# 03_-Main_Processor.net
KiCad netlist of a schematic drawn in Altium Designer
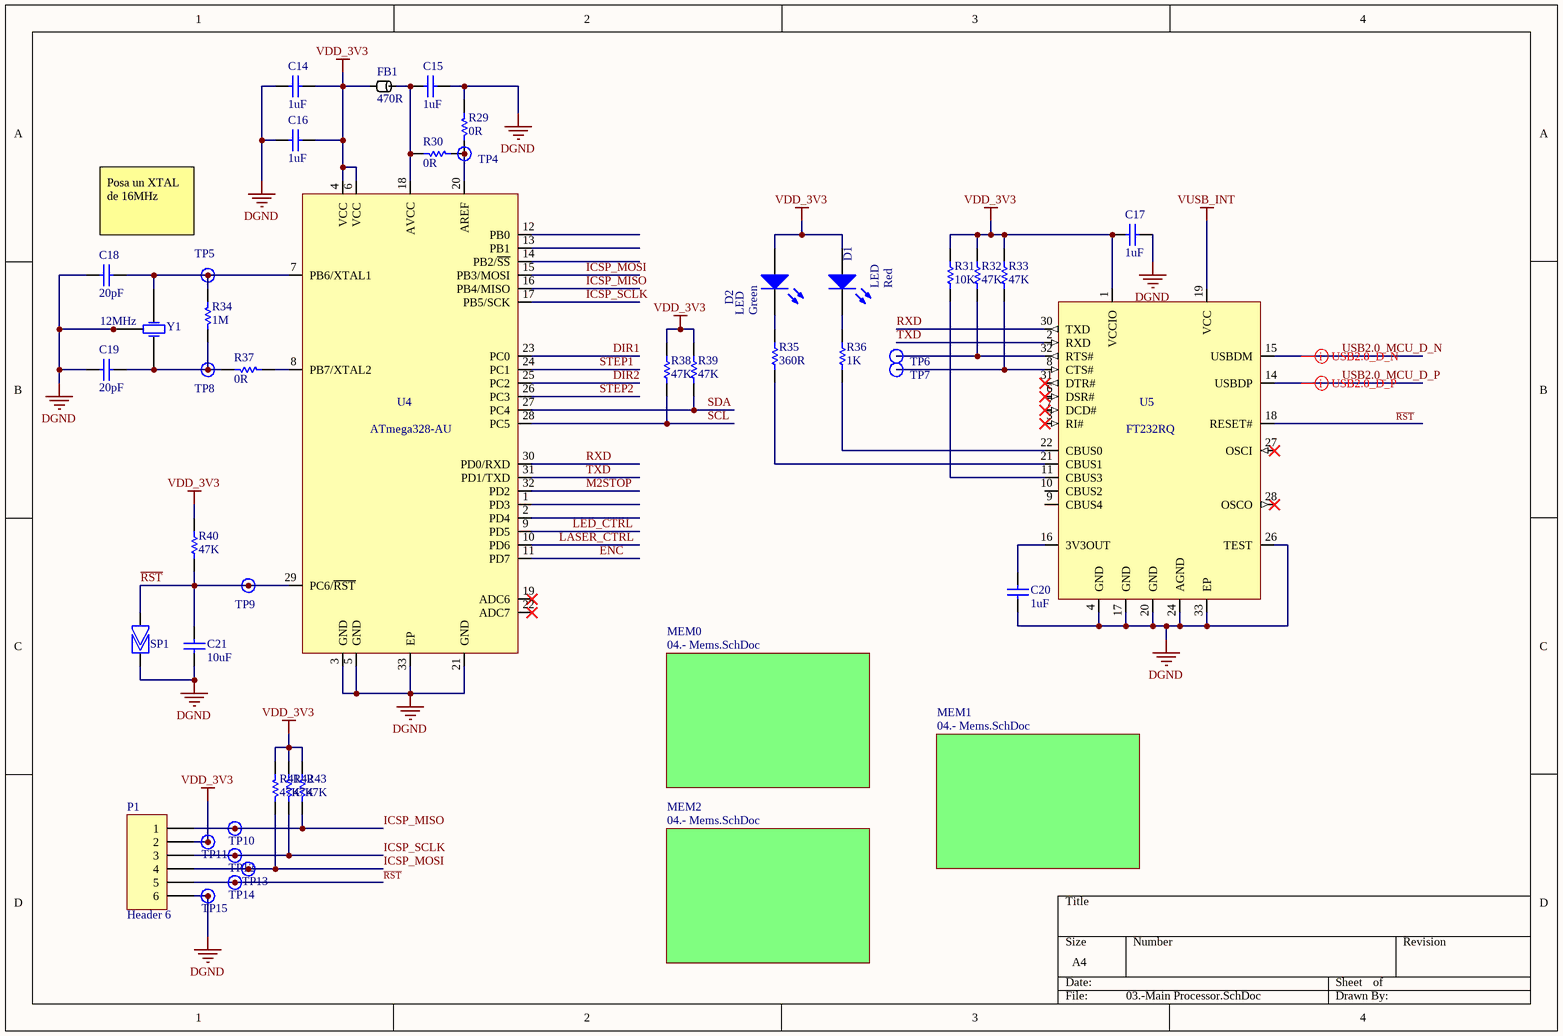
[diagram p0: 03.-Main Processor.SchDoc]

(export (version "E")
  (design (tool "Eeschema 10.0.6"))
  (components
    (comp (ref "C14")
      (value "1uF")
      (footprint "CAPC1005N")
      (description "COND. CER.1uF X5R 16V 0402")
      (fields
        (field (name "PART NUMBER") "ISR01020111")
        (field (name "VOLTAGE") "16V")
        (field (name "PUBLISHER") "Altium Limited")
        (field (name "LIBRARY PATH") "SIMBOLS_PASSIUS.SCHLIB")
      )
      (libsource (lib "MAIN_CSE") (part "CAP-NP"))
    )
    (comp (ref "C15")
      (value "1uF")
      (footprint "CAPC1005N")
      (description "COND. CER.1uF X5R 16V 0402")
      (fields
        (field (name "PART NUMBER") "ISR01020111")
        (field (name "VOLTAGE") "16V")
        (field (name "PUBLISHER") "Altium Limited")
        (field (name "LIBRARY PATH") "SIMBOLS_PASSIUS.SCHLIB")
      )
      (libsource (lib "MAIN_CSE") (part "CAP-NP"))
    )
    (comp (ref "C16")
      (value "1uF")
      (footprint "CAPC1005N")
      (description "COND. CER.1uF X5R 16V 0402")
      (fields
        (field (name "PART NUMBER") "ISR01020111")
        (field (name "VOLTAGE") "16V")
        (field (name "PUBLISHER") "Altium Limited")
        (field (name "LIBRARY PATH") "SIMBOLS_PASSIUS.SCHLIB")
      )
      (libsource (lib "MAIN_CSE") (part "CAP-NP"))
    )
    (comp (ref "C17")
      (value "1uF")
      (footprint "CAPC1005N")
      (description "COND. CER.1uF X5R 16V 0402")
      (fields
        (field (name "PART NUMBER") "ISR01020111")
        (field (name "VOLTAGE") "16V")
        (field (name "PUBLISHER") "Altium Limited")
        (field (name "LIBRARY PATH") "SIMBOLS_PASSIUS.SCHLIB")
      )
      (libsource (lib "MAIN_CSE") (part "CAP-NP"))
    )
    (comp (ref "C18")
      (value "20pF")
      (footprint "CAPC1608N")
      (description "COND. SMD 20P COG 50V 0603")
      (fields
        (field (name "PART NUMBER") "ISR01020103")
        (field (name "VOLTAGE") "50V")
        (field (name "PUBLISHER") "Altium Limited")
        (field (name "LIBRARY PATH") "SIMBOLS_PASSIUS.SCHLIB")
      )
      (libsource (lib "MAIN_CSE") (part "CAP-NP"))
    )
    (comp (ref "C19")
      (value "20pF")
      (footprint "CAPC1608N")
      (description "COND. SMD 20P COG 50V 0603")
      (fields
        (field (name "PART NUMBER") "ISR01020103")
        (field (name "VOLTAGE") "50V")
        (field (name "PUBLISHER") "Altium Limited")
        (field (name "LIBRARY PATH") "SIMBOLS_PASSIUS.SCHLIB")
      )
      (libsource (lib "MAIN_CSE") (part "CAP-NP"))
    )
    (comp (ref "C20")
      (value "1uF")
      (footprint "CAPC1005N")
      (description "COND. CER.1uF X5R 16V 0402")
      (fields
        (field (name "PART NUMBER") "ISR01020111")
        (field (name "VOLTAGE") "16V")
        (field (name "PUBLISHER") "Altium Limited")
        (field (name "LIBRARY PATH") "SIMBOLS_PASSIUS.SCHLIB")
      )
      (libsource (lib "MAIN_CSE") (part "CAP-NP"))
    )
    (comp (ref "C21")
      (value "10uF")
      (footprint "CAPC1608N")
      (description "COND. SMD 10uF X5R 6V3 0603")
      (fields
        (field (name "PART NUMBER") "ISR01020094")
        (field (name "VOLTAGE") "6V3")
        (field (name "PUBLISHER") "Altium Limited")
        (field (name "LIBRARY PATH") "SIMBOLS_PASSIUS.SCHLIB")
      )
      (libsource (lib "MAIN_CSE") (part "CAP-NP"))
    )
    (comp (ref "D1")
      (value "LED")
      (footprint "LED_1206")
      (description "LUXEON Z Vermell 1A 3.15V")
      (fields
        (field (name "PART NUMBER") "LXZ1-PD01")
        (field (name "COLOR1") "Red")
        (field (name "LIBRARY PATH") "SIMBOLS_SEMICONDUCTORS.SCHLIB")
      )
      (libsource (lib "MAIN_CSE") (part "LED"))
    )
    (comp (ref "D2")
      (value "LED")
      (footprint "LED_1206")
      (description "LUXEON Z Verd 1A 3.15V")
      (fields
        (field (name "PART NUMBER") "LXZ1-PM01")
        (field (name "COLOR1") "Green")
        (field (name "LIBRARY PATH") "SIMBOLS_SEMICONDUCTORS.SCHLIB")
      )
      (libsource (lib "MAIN_CSE") (part "LED"))
    )
    (comp (ref "FB1")
      (value "470R")
      (footprint "INDC1608M")
      (description "Ferrita SMD 470R@100MHz 25% 1A 0603")
      (fields
        (field (name "PART NUMBER") "BLM18PG471SN1p")
        (field (name "TOLERANCE") "25%")
        (field (name "LIBRARY PATH") "SIMBOLS_PASSIUS.SCHLIB")
      )
      (libsource (lib "MAIN_CSE") (part "FERRITA"))
    )
    (comp (ref "P1")
      (value "Header 6")
      (footprint "HDR1X6")
      (description "Header, 6-Pin")
      (fields (field (name "PUBLISHER") "Altium Limited"))
      (libsource (lib "MAIN_CSE") (part "Header 6"))
    )
    (comp (ref "R29")
      (value "0R")
      (footprint "RESC1005M")
      (description "Resistencia SMD 0402 1% 0R")
      (fields
        (field (name "PART NUMBER") "ISR01010776")
        (field (name "TOLERANCE") "1%")
        (field (name "PUBLISHER") "Altium Limited")
        (field (name "LIBRARY PATH") "SIMBOLS_PASSIUS.SCHLIB")
      )
      (libsource (lib "MAIN_CSE") (part "RESISTOR"))
    )
    (comp (ref "R30")
      (value "0R")
      (footprint "RESC1005M")
      (description "Resistencia SMD 0402 1% 0R")
      (fields
        (field (name "PART NUMBER") "ISR01010776")
        (field (name "TOLERANCE") "1%")
        (field (name "PUBLISHER") "Altium Limited")
        (field (name "LIBRARY PATH") "SIMBOLS_PASSIUS.SCHLIB")
      )
      (libsource (lib "MAIN_CSE") (part "RESISTOR"))
    )
    (comp (ref "R31")
      (value "10K")
      (footprint "RESC1608M")
      (description "Resistencia SMD 0603 5% 10K")
      (fields
        (field (name "PART NUMBER") "ISR01010121")
        (field (name "TOLERANCE") "5%")
        (field (name "PUBLISHER") "Altium Limited")
        (field (name "LIBRARY PATH") "SIMBOLS_PASSIUS.SCHLIB")
      )
      (libsource (lib "MAIN_CSE") (part "RESISTOR"))
    )
    (comp (ref "R32")
      (value "47K")
      (footprint "RESC1005M")
      (description "Resistencia SMD 0402 1% 47K")
      (fields
        (field (name "TOLERANCE") "1%")
        (field (name "PART NUMBER") "ISR01010913")
        (field (name "PUBLISHER") "Altium Limited")
        (field (name "LIBRARY PATH") "SIMBOLS_PASSIUS.SCHLIB")
      )
      (libsource (lib "MAIN_CSE") (part "RESISTOR"))
    )
    (comp (ref "R33")
      (value "47K")
      (footprint "RESC1005M")
      (description "Resistencia SMD 0402 1% 47K")
      (fields
        (field (name "TOLERANCE") "1%")
        (field (name "PART NUMBER") "ISR01010913")
        (field (name "PUBLISHER") "Altium Limited")
        (field (name "LIBRARY PATH") "SIMBOLS_PASSIUS.SCHLIB")
      )
      (libsource (lib "MAIN_CSE") (part "RESISTOR"))
    )
    (comp (ref "R34")
      (value "1M")
      (footprint "RESC1608M")
      (description "Resistencia SMD 0603 5% 1M")
      (fields
        (field (name "TOLERANCE") "5%")
        (field (name "PART NUMBER") "ISR01010169")
        (field (name "PUBLISHER") "Altium Limited")
        (field (name "LIBRARY PATH") "SIMBOLS_PASSIUS.SCHLIB")
      )
      (libsource (lib "MAIN_CSE") (part "RESISTOR"))
    )
    (comp (ref "R35")
      (value "360R")
      (footprint "RESC1608M")
      (description "Resistencia SMD 0603 5% 360R")
      (fields
        (field (name "PART NUMBER") "ISR01010086")
        (field (name "TOLERANCE") "5%")
        (field (name "PUBLISHER") "Altium Limited")
        (field (name "LIBRARY PATH") "SIMBOLS_PASSIUS.SCHLIB")
      )
      (libsource (lib "MAIN_CSE") (part "RESISTOR"))
    )
    (comp (ref "R36")
      (value "1K")
      (footprint "RESC1608M")
      (description "Resistencia SMD 0603 5% 1K")
      (fields
        (field (name "PART NUMBER") "ISR01010097")
        (field (name "TOLERANCE") "5%")
        (field (name "PUBLISHER") "Altium Limited")
        (field (name "LIBRARY PATH") "SIMBOLS_PASSIUS.SCHLIB")
      )
      (libsource (lib "MAIN_CSE") (part "RESISTOR"))
    )
    (comp (ref "R37")
      (value "0R")
      (footprint "RESC1005M")
      (description "Resistencia SMD 0402 1% 0R")
      (fields
        (field (name "PART NUMBER") "ISR01010776")
        (field (name "TOLERANCE") "1%")
        (field (name "PUBLISHER") "Altium Limited")
        (field (name "LIBRARY PATH") "SIMBOLS_PASSIUS.SCHLIB")
      )
      (libsource (lib "MAIN_CSE") (part "RESISTOR"))
    )
    (comp (ref "R38")
      (value "47K")
      (footprint "RESC1005M")
      (description "Resistencia SMD 0402 1% 47K")
      (fields
        (field (name "TOLERANCE") "1%")
        (field (name "PART NUMBER") "ISR01010913")
        (field (name "PUBLISHER") "Altium Limited")
        (field (name "LIBRARY PATH") "SIMBOLS_PASSIUS.SCHLIB")
      )
      (libsource (lib "MAIN_CSE") (part "RESISTOR"))
    )
    (comp (ref "R39")
      (value "47K")
      (footprint "RESC1005M")
      (description "Resistencia SMD 0402 1% 47K")
      (fields
        (field (name "TOLERANCE") "1%")
        (field (name "PART NUMBER") "ISR01010913")
        (field (name "PUBLISHER") "Altium Limited")
        (field (name "LIBRARY PATH") "SIMBOLS_PASSIUS.SCHLIB")
      )
      (libsource (lib "MAIN_CSE") (part "RESISTOR"))
    )
    (comp (ref "R40")
      (value "47K")
      (footprint "RESC1005M")
      (description "Resistencia SMD 0402 1% 47K")
      (fields
        (field (name "TOLERANCE") "1%")
        (field (name "PART NUMBER") "ISR01010913")
        (field (name "PUBLISHER") "Altium Limited")
        (field (name "LIBRARY PATH") "SIMBOLS_PASSIUS.SCHLIB")
      )
      (libsource (lib "MAIN_CSE") (part "RESISTOR"))
    )
    (comp (ref "R41")
      (value "47K")
      (footprint "RESC1005M")
      (description "Resistencia SMD 0402 1% 47K")
      (fields
        (field (name "TOLERANCE") "1%")
        (field (name "PART NUMBER") "ISR01010913")
        (field (name "PUBLISHER") "Altium Limited")
        (field (name "LIBRARY PATH") "SIMBOLS_PASSIUS.SCHLIB")
      )
      (libsource (lib "MAIN_CSE") (part "RESISTOR"))
    )
    (comp (ref "R42")
      (value "47K")
      (footprint "RESC1005M")
      (description "Resistencia SMD 0402 1% 47K")
      (fields
        (field (name "TOLERANCE") "1%")
        (field (name "PART NUMBER") "ISR01010913")
        (field (name "PUBLISHER") "Altium Limited")
        (field (name "LIBRARY PATH") "SIMBOLS_PASSIUS.SCHLIB")
      )
      (libsource (lib "MAIN_CSE") (part "RESISTOR"))
    )
    (comp (ref "R43")
      (value "47K")
      (footprint "RESC1005M")
      (description "Resistencia SMD 0402 1% 47K")
      (fields
        (field (name "TOLERANCE") "1%")
        (field (name "PART NUMBER") "ISR01010913")
        (field (name "PUBLISHER") "Altium Limited")
        (field (name "LIBRARY PATH") "SIMBOLS_PASSIUS.SCHLIB")
      )
      (libsource (lib "MAIN_CSE") (part "RESISTOR"))
    )
    (comp (ref "SP1")
      (value "SOLDERPAD_2")
      (footprint "SOLDERPAD_2")
      (fields (field (name "LIBRARY PATH") "SIMBOLS_CONNECTORS.SCHLIB"))
      (libsource (lib "MAIN_CSE") (part "SOLDERPAD_2"))
    )
    (comp (ref "TP4")
      (value "TESTPOINT")
      (footprint "TestPoint")
      (description "TEST POINT INLINE")
      (fields
        (field (name "PART NUMBER") "STP0003")
        (field (name "LIBRARY PATH") "SIMBOLS_CONNECTORS.SCHLIB")
      )
      (libsource (lib "MAIN_CSE") (part "TESTPOINT"))
    )
    (comp (ref "TP5")
      (value "TESTPOINT")
      (footprint "TestPoint")
      (description "TEST POINT INLINE")
      (fields
        (field (name "PART NUMBER") "STP0003")
        (field (name "LIBRARY PATH") "SIMBOLS_CONNECTORS.SCHLIB")
      )
      (libsource (lib "MAIN_CSE") (part "TESTPOINT"))
    )
    (comp (ref "TP6")
      (value "TESTPOINT")
      (footprint "TestPoint")
      (description "TEST POINT INLINE")
      (fields
        (field (name "PART NUMBER") "STP0003")
        (field (name "LIBRARY PATH") "SIMBOLS_CONNECTORS.SCHLIB")
      )
      (libsource (lib "MAIN_CSE") (part "TESTPOINT"))
    )
    (comp (ref "TP7")
      (value "TESTPOINT")
      (footprint "TestPoint")
      (description "TEST POINT INLINE")
      (fields
        (field (name "PART NUMBER") "STP0003")
        (field (name "LIBRARY PATH") "SIMBOLS_CONNECTORS.SCHLIB")
      )
      (libsource (lib "MAIN_CSE") (part "TESTPOINT"))
    )
    (comp (ref "TP8")
      (value "TESTPOINT")
      (footprint "TestPoint")
      (description "TEST POINT INLINE")
      (fields
        (field (name "PART NUMBER") "STP0003")
        (field (name "LIBRARY PATH") "SIMBOLS_CONNECTORS.SCHLIB")
      )
      (libsource (lib "MAIN_CSE") (part "TESTPOINT"))
    )
    (comp (ref "TP9")
      (value "TESTPOINT")
      (footprint "TestPoint")
      (description "TEST POINT INLINE")
      (fields
        (field (name "PART NUMBER") "STP0003")
        (field (name "LIBRARY PATH") "SIMBOLS_CONNECTORS.SCHLIB")
      )
      (libsource (lib "MAIN_CSE") (part "TESTPOINT"))
    )
    (comp (ref "TP10")
      (value "TESTPOINT")
      (footprint "TestPoint")
      (description "TEST POINT INLINE")
      (fields
        (field (name "PART NUMBER") "STP0003")
        (field (name "LIBRARY PATH") "SIMBOLS_CONNECTORS.SCHLIB")
      )
      (libsource (lib "MAIN_CSE") (part "TESTPOINT"))
    )
    (comp (ref "TP11")
      (value "TESTPOINT")
      (footprint "TestPoint")
      (description "TEST POINT INLINE")
      (fields
        (field (name "PART NUMBER") "STP0003")
        (field (name "LIBRARY PATH") "SIMBOLS_CONNECTORS.SCHLIB")
      )
      (libsource (lib "MAIN_CSE") (part "TESTPOINT"))
    )
    (comp (ref "TP12")
      (value "TESTPOINT")
      (footprint "TestPoint")
      (description "TEST POINT INLINE")
      (fields
        (field (name "PART NUMBER") "STP0003")
        (field (name "LIBRARY PATH") "SIMBOLS_CONNECTORS.SCHLIB")
      )
      (libsource (lib "MAIN_CSE") (part "TESTPOINT"))
    )
    (comp (ref "TP13")
      (value "TESTPOINT")
      (footprint "TestPoint")
      (description "TEST POINT INLINE")
      (fields
        (field (name "PART NUMBER") "STP0003")
        (field (name "LIBRARY PATH") "SIMBOLS_CONNECTORS.SCHLIB")
      )
      (libsource (lib "MAIN_CSE") (part "TESTPOINT"))
    )
    (comp (ref "TP14")
      (value "TESTPOINT")
      (footprint "TestPoint")
      (description "TEST POINT INLINE")
      (fields
        (field (name "PART NUMBER") "STP0003")
        (field (name "LIBRARY PATH") "SIMBOLS_CONNECTORS.SCHLIB")
      )
      (libsource (lib "MAIN_CSE") (part "TESTPOINT"))
    )
    (comp (ref "TP15")
      (value "TESTPOINT")
      (footprint "TestPoint")
      (description "TEST POINT INLINE")
      (fields
        (field (name "PART NUMBER") "STP0003")
        (field (name "LIBRARY PATH") "SIMBOLS_CONNECTORS.SCHLIB")
      )
      (libsource (lib "MAIN_CSE") (part "TESTPOINT"))
    )
    (comp (ref "U4")
      (value "ATmega328-AU")
      (footprint "TQFP80P900X900-32L")
      (description "ATMEL 8-BIT MICROCONTROLLER WITH 32KBYTES IN-SYSTEM PROGRAMMABLE FLASH  TQFP32")
      (fields (field (name "VOLTAGE") "1V8-5V5") (field (name "LIBRARY PATH") "SIMBOLS_CPU_MCU.SCHLIB"))
      (libsource (lib "MAIN_CSE") (part "Atmega328_32P"))
    )
    (comp (ref "U5")
      (value "FT232RQ")
      (footprint "QFN50P500X500-32VAN")
      (description "USB-TO-UART, SMD, 32LQFP")
      (libsource (lib "MAIN_CSE") (part "FT232RQ"))
    )
    (comp (ref "Y1")
      (value "12MHz")
      (footprint "Oscillator 3,2 x 2,5 4pin")
      (description "CRISTALL SMD 12MHz 30ppm 3V3 18pF")
      (fields
        (field (name "PARTNO") "403C35D12M00000")
        (field (name "VOLTAGE") "3V3")
        (field (name "LIBRARY PATH") "SIMBOLS_FREQ.SCHLIB")
      )
      (libsource (lib "MAIN_CSE") (part "XTAL-4P (2GND)"))
    )
  )
  (nets
    (net (code "1") (name "/DIR1") (class "Default")
      (node (ref "U4") (pin "23") (pinfunction "PC0_23") (pintype "passive"))
    )
    (net (code "2") (name "/DIR2") (class "Default")
      (node (ref "U4") (pin "25") (pinfunction "PC2_25") (pintype "passive"))
    )
    (net (code "3") (name "/ENC") (class "Default")
      (node (ref "U4") (pin "11") (pinfunction "PD7_11") (pintype "passive"))
    )
    (net (code "4") (name "/ICSP_MISO") (class "Default")
      (node (ref "P1") (pin "1") (pinfunction "1_1") (pintype "passive"))
      (node (ref "R43") (pin "1") (pinfunction "1_1") (pintype "passive"))
      (node (ref "TP10") (pin "1") (pinfunction "1_1") (pintype "passive"))
      (node (ref "U4") (pin "16") (pinfunction "PB4/MISO_16") (pintype "passive"))
    )
    (net (code "5") (name "/ICSP_MOSI") (class "Default")
      (node (ref "P1") (pin "4") (pinfunction "4_4") (pintype "passive"))
      (node (ref "R41") (pin "1") (pinfunction "1_1") (pintype "passive"))
      (node (ref "TP13") (pin "1") (pinfunction "1_1") (pintype "passive"))
      (node (ref "U4") (pin "15") (pinfunction "PB3/MOSI_15") (pintype "passive"))
    )
    (net (code "6") (name "/ICSP_SCLK") (class "Default")
      (node (ref "P1") (pin "3") (pinfunction "3_3") (pintype "passive"))
      (node (ref "R42") (pin "1") (pinfunction "1_1") (pintype "passive"))
      (node (ref "TP12") (pin "1") (pinfunction "1_1") (pintype "passive"))
      (node (ref "U4") (pin "17") (pinfunction "PB5/SCK_17") (pintype "passive"))
    )
    (net (code "7") (name "/LASER_CTRL") (class "Default")
      (node (ref "U4") (pin "10") (pinfunction "PD6_10") (pintype "passive"))
    )
    (net (code "8") (name "/LED_CTRL") (class "Default")
      (node (ref "U4") (pin "9") (pinfunction "PD5_9") (pintype "passive"))
    )
    (net (code "9") (name "/M2STOP") (class "Default")
      (node (ref "U4") (pin "32") (pinfunction "PD2_32") (pintype "passive"))
    )
    (net (code "10") (name "/RXD") (class "Default")
      (node (ref "U4") (pin "30") (pinfunction "PD0/RXD_30") (pintype "passive"))
      (node (ref "U5") (pin "30") (pinfunction "TXD_30") (pintype "output"))
    )
    (net (code "11") (name "/SCL") (class "Default")
      (node (ref "R38") (pin "1") (pinfunction "1_1") (pintype "passive"))
      (node (ref "U4") (pin "28") (pinfunction "PC5_28") (pintype "passive"))
    )
    (net (code "12") (name "/SDA") (class "Default")
      (node (ref "R39") (pin "1") (pinfunction "1_1") (pintype "passive"))
      (node (ref "U4") (pin "27") (pinfunction "PC4_27") (pintype "passive"))
    )
    (net (code "13") (name "/STEP1") (class "Default")
      (node (ref "U4") (pin "24") (pinfunction "PC1_24") (pintype "passive"))
    )
    (net (code "14") (name "/STEP2") (class "Default")
      (node (ref "U4") (pin "26") (pinfunction "PC3_26") (pintype "passive"))
    )
    (net (code "15") (name "/TXD") (class "Default")
      (node (ref "U4") (pin "31") (pinfunction "PD1/TXD_31") (pintype "passive"))
      (node (ref "U5") (pin "2") (pinfunction "RXD_2") (pintype "input"))
    )
    (net (code "16") (name "/USB2.0_MCU_D_N") (class "Default")
      (node (ref "U5") (pin "15") (pinfunction "USBDM_15") (pintype "bidirectional"))
    )
    (net (code "17") (name "/USB2.0_MCU_D_P") (class "Default")
      (node (ref "U5") (pin "14") (pinfunction "USBDP_14") (pintype "bidirectional"))
    )
    (net (code "18") (name "/~{RST}") (class "Default")
      (node (ref "C21") (pin "2") (pinfunction "2_2") (pintype "passive"))
      (node (ref "P1") (pin "5") (pinfunction "5_5") (pintype "passive"))
      (node (ref "R40") (pin "1") (pinfunction "1_1") (pintype "passive"))
      (node (ref "SP1") (pin "2") (pinfunction "2_2") (pintype "passive"))
      (node (ref "TP14") (pin "1") (pinfunction "1_1") (pintype "passive"))
      (node (ref "TP9") (pin "1") (pinfunction "1_1") (pintype "passive"))
      (node (ref "U4") (pin "29") (pinfunction "PC6/~{RST}_29") (pintype "passive"))
      (node (ref "U5") (pin "18") (pinfunction "RESET#_18") (pintype "passive"))
    )
    (net (code "19") (name "DGND") (class "Default")
      (node (ref "C14") (pin "1") (pinfunction "1_1") (pintype "passive"))
      (node (ref "C15") (pin "2") (pinfunction "2_2") (pintype "passive"))
      (node (ref "C16") (pin "2") (pinfunction "2_2") (pintype "passive"))
      (node (ref "C17") (pin "2") (pinfunction "2_2") (pintype "passive"))
      (node (ref "C18") (pin "1") (pinfunction "1_1") (pintype "passive"))
      (node (ref "C19") (pin "1") (pinfunction "1_1") (pintype "passive"))
      (node (ref "C20") (pin "1") (pinfunction "1_1") (pintype "passive"))
      (node (ref "C21") (pin "1") (pinfunction "1_1") (pintype "passive"))
      (node (ref "P1") (pin "6") (pinfunction "6_6") (pintype "passive"))
      (node (ref "R29") (pin "1") (pinfunction "1_1") (pintype "passive"))
      (node (ref "SP1") (pin "1") (pinfunction "1_1") (pintype "passive"))
      (node (ref "TP15") (pin "1") (pinfunction "1_1") (pintype "passive"))
      (node (ref "U4") (pin "21") (pinfunction "GND_21") (pintype "passive"))
      (node (ref "U4") (pin "3") (pinfunction "GND_3") (pintype "passive"))
      (node (ref "U4") (pin "33") (pinfunction "EP_33") (pintype "passive"))
      (node (ref "U4") (pin "5") (pinfunction "GND_5") (pintype "passive"))
      (node (ref "U5") (pin "17") (pinfunction "GND_17") (pintype "passive"))
      (node (ref "U5") (pin "20") (pinfunction "GND_20") (pintype "passive"))
      (node (ref "U5") (pin "24") (pinfunction "AGND_24") (pintype "passive"))
      (node (ref "U5") (pin "26") (pinfunction "TEST_26") (pintype "passive"))
      (node (ref "U5") (pin "33") (pinfunction "EP_33") (pintype "passive"))
      (node (ref "U5") (pin "4") (pinfunction "GND_4") (pintype "passive"))
      (node (ref "Y1") (pin "2") (pinfunction "IO1-1_2") (pintype "passive"))
      (node (ref "Y1") (pin "4") (pinfunction "IO1-1_4") (pintype "passive"))
    )
    (net (code "20") (name "Net-(C19-Pad2)") (class "Default")
      (node (ref "C19") (pin "2") (pinfunction "2_2") (pintype "passive"))
      (node (ref "R34") (pin "1") (pinfunction "1_1") (pintype "passive"))
      (node (ref "R37") (pin "2") (pinfunction "2_2") (pintype "passive"))
      (node (ref "TP8") (pin "1") (pinfunction "1_1") (pintype "passive"))
      (node (ref "Y1") (pin "3") (pinfunction "IO1-1_3") (pintype "passive"))
    )
    (net (code "21") (name "Net-(D1-K)") (class "Default")
      (node (ref "D1") (pin "2") (pinfunction "K_2") (pintype "passive"))
      (node (ref "R36") (pin "2") (pinfunction "2_2") (pintype "passive"))
    )
    (net (code "22") (name "Net-(D2-K)") (class "Default")
      (node (ref "D2") (pin "2") (pinfunction "K_2") (pintype "passive"))
      (node (ref "R35") (pin "2") (pinfunction "2_2") (pintype "passive"))
    )
    (net (code "23") (name "Net-(U4-AREF)") (class "Default")
      (node (ref "R29") (pin "2") (pinfunction "2_2") (pintype "passive"))
      (node (ref "R30") (pin "1") (pinfunction "1_1") (pintype "passive"))
      (node (ref "TP4") (pin "1") (pinfunction "1_1") (pintype "passive"))
      (node (ref "U4") (pin "20") (pinfunction "AREF_20") (pintype "passive"))
    )
    (net (code "24") (name "Net-(U4-AVCC)") (class "Default")
      (node (ref "C15") (pin "1") (pinfunction "1_1") (pintype "passive"))
      (node (ref "FB1") (pin "1") (pinfunction "1_1") (pintype "passive"))
      (node (ref "R30") (pin "2") (pinfunction "2_2") (pintype "passive"))
      (node (ref "U4") (pin "18") (pinfunction "AVCC_18") (pintype "passive"))
    )
    (net (code "25") (name "Net-(U4-PB6{slash}XTAL1)") (class "Default")
      (node (ref "C18") (pin "2") (pinfunction "2_2") (pintype "passive"))
      (node (ref "R34") (pin "2") (pinfunction "2_2") (pintype "passive"))
      (node (ref "TP5") (pin "1") (pinfunction "1_1") (pintype "passive"))
      (node (ref "U4") (pin "7") (pinfunction "PB6/XTAL1_7") (pintype "passive"))
      (node (ref "Y1") (pin "1") (pinfunction "IO1-1_1") (pintype "passive"))
    )
    (net (code "26") (name "Net-(U4-PB7{slash}XTAL2)") (class "Default")
      (node (ref "R37") (pin "1") (pinfunction "1_1") (pintype "passive"))
      (node (ref "U4") (pin "8") (pinfunction "PB7/XTAL2_8") (pintype "passive"))
    )
    (net (code "27") (name "Net-(U5-3V3OUT)") (class "Default")
      (node (ref "C20") (pin "2") (pinfunction "2_2") (pintype "passive"))
      (node (ref "U5") (pin "16") (pinfunction "3V3OUT_16") (pintype "passive"))
    )
    (net (code "28") (name "Net-(U5-CBUS0)") (class "Default")
      (node (ref "R36") (pin "1") (pinfunction "1_1") (pintype "passive"))
      (node (ref "U5") (pin "22") (pinfunction "CBUS0_22") (pintype "passive"))
    )
    (net (code "29") (name "Net-(U5-CBUS1)") (class "Default")
      (node (ref "R35") (pin "1") (pinfunction "1_1") (pintype "passive"))
      (node (ref "U5") (pin "21") (pinfunction "CBUS1_21") (pintype "passive"))
    )
    (net (code "30") (name "Net-(U5-CBUS3)") (class "Default")
      (node (ref "R31") (pin "1") (pinfunction "1_1") (pintype "passive"))
      (node (ref "U5") (pin "11") (pinfunction "CBUS3_11") (pintype "passive"))
    )
    (net (code "31") (name "Net-(U5-CTS#)") (class "Default")
      (node (ref "R33") (pin "1") (pinfunction "1_1") (pintype "passive"))
      (node (ref "TP7") (pin "1") (pinfunction "1_1") (pintype "passive"))
      (node (ref "U5") (pin "8") (pinfunction "CTS#_8") (pintype "input"))
    )
    (net (code "32") (name "Net-(U5-RTS#)") (class "Default")
      (node (ref "R32") (pin "1") (pinfunction "1_1") (pintype "passive"))
      (node (ref "TP6") (pin "1") (pinfunction "1_1") (pintype "passive"))
      (node (ref "U5") (pin "32") (pinfunction "RTS#_32") (pintype "output"))
    )
    (net (code "33") (name "VDD_3V3") (class "Default")
      (node (ref "C14") (pin "2") (pinfunction "2_2") (pintype "passive"))
      (node (ref "C16") (pin "1") (pinfunction "1_1") (pintype "passive"))
      (node (ref "C17") (pin "1") (pinfunction "1_1") (pintype "passive"))
      (node (ref "D1") (pin "1") (pinfunction "A_1") (pintype "passive"))
      (node (ref "D2") (pin "1") (pinfunction "A_1") (pintype "passive"))
      (node (ref "FB1") (pin "2") (pinfunction "2_2") (pintype "passive"))
      (node (ref "P1") (pin "2") (pinfunction "2_2") (pintype "passive"))
      (node (ref "R31") (pin "2") (pinfunction "2_2") (pintype "passive"))
      (node (ref "R32") (pin "2") (pinfunction "2_2") (pintype "passive"))
      (node (ref "R33") (pin "2") (pinfunction "2_2") (pintype "passive"))
      (node (ref "R38") (pin "2") (pinfunction "2_2") (pintype "passive"))
      (node (ref "R39") (pin "2") (pinfunction "2_2") (pintype "passive"))
      (node (ref "R40") (pin "2") (pinfunction "2_2") (pintype "passive"))
      (node (ref "R41") (pin "2") (pinfunction "2_2") (pintype "passive"))
      (node (ref "R42") (pin "2") (pinfunction "2_2") (pintype "passive"))
      (node (ref "R43") (pin "2") (pinfunction "2_2") (pintype "passive"))
      (node (ref "TP11") (pin "1") (pinfunction "1_1") (pintype "passive"))
      (node (ref "U4") (pin "4") (pinfunction "VCC_4") (pintype "passive"))
      (node (ref "U4") (pin "6") (pinfunction "VCC_6") (pintype "passive"))
      (node (ref "U5") (pin "1") (pinfunction "VCCIO_1") (pintype "passive"))
    )
    (net (code "34") (name "VUSB_INT") (class "Default")
      (node (ref "U5") (pin "19") (pinfunction "VCC_19") (pintype "passive"))
    )
    (net (code "35") (name "unconnected-(U4-ADC6-Pad19)") (class "Default")
      (node (ref "U4") (pin "19") (pinfunction "ADC6_19") (pintype "passive+no_connect"))
    )
    (net (code "36") (name "unconnected-(U4-ADC7-Pad22)") (class "Default")
      (node (ref "U4") (pin "22") (pinfunction "ADC7_22") (pintype "passive+no_connect"))
    )
    (net (code "37") (name "unconnected-(U4-PB0-Pad12)") (class "Default")
      (node (ref "U4") (pin "12") (pinfunction "PB0_12") (pintype "passive"))
    )
    (net (code "38") (name "unconnected-(U4-PB1-Pad13)") (class "Default")
      (node (ref "U4") (pin "13") (pinfunction "PB1_13") (pintype "passive"))
    )
    (net (code "39") (name "unconnected-(U4-PB2{slash}~{SS}-Pad14)") (class "Default")
      (node (ref "U4") (pin "14") (pinfunction "PB2/~{SS}_14") (pintype "passive"))
    )
    (net (code "40") (name "unconnected-(U4-PD3-Pad1)") (class "Default")
      (node (ref "U4") (pin "1") (pinfunction "PD3_1") (pintype "passive"))
    )
    (net (code "41") (name "unconnected-(U4-PD4-Pad2)") (class "Default")
      (node (ref "U4") (pin "2") (pinfunction "PD4_2") (pintype "passive"))
    )
    (net (code "42") (name "unconnected-(U5-CBUS2-Pad10)") (class "Default")
      (node (ref "U5") (pin "10") (pinfunction "CBUS2_10") (pintype "passive"))
    )
    (net (code "43") (name "unconnected-(U5-CBUS4-Pad9)") (class "Default")
      (node (ref "U5") (pin "9") (pinfunction "CBUS4_9") (pintype "passive"))
    )
    (net (code "44") (name "unconnected-(U5-DCD#-Pad7)") (class "Default")
      (node (ref "U5") (pin "7") (pinfunction "DCD#_7") (pintype "input+no_connect"))
    )
    (net (code "45") (name "unconnected-(U5-DSR#-Pad6)") (class "Default")
      (node (ref "U5") (pin "6") (pinfunction "DSR#_6") (pintype "input+no_connect"))
    )
    (net (code "46") (name "unconnected-(U5-DTR#-Pad31)") (class "Default")
      (node (ref "U5") (pin "31") (pinfunction "DTR#_31") (pintype "output+no_connect"))
    )
    (net (code "47") (name "unconnected-(U5-OSCI-Pad27)") (class "Default")
      (node (ref "U5") (pin "27") (pinfunction "OSCI_27") (pintype "input+no_connect"))
    )
    (net (code "48") (name "unconnected-(U5-OSCO-Pad28)") (class "Default")
      (node (ref "U5") (pin "28") (pinfunction "OSCO_28") (pintype "output+no_connect"))
    )
    (net (code "49") (name "unconnected-(U5-RI#-Pad3)") (class "Default")
      (node (ref "U5") (pin "3") (pinfunction "RI#_3") (pintype "input+no_connect"))
    )
  )
)
